# sensor.net
KiCad netlist of a schematic drawn in Altium Designer
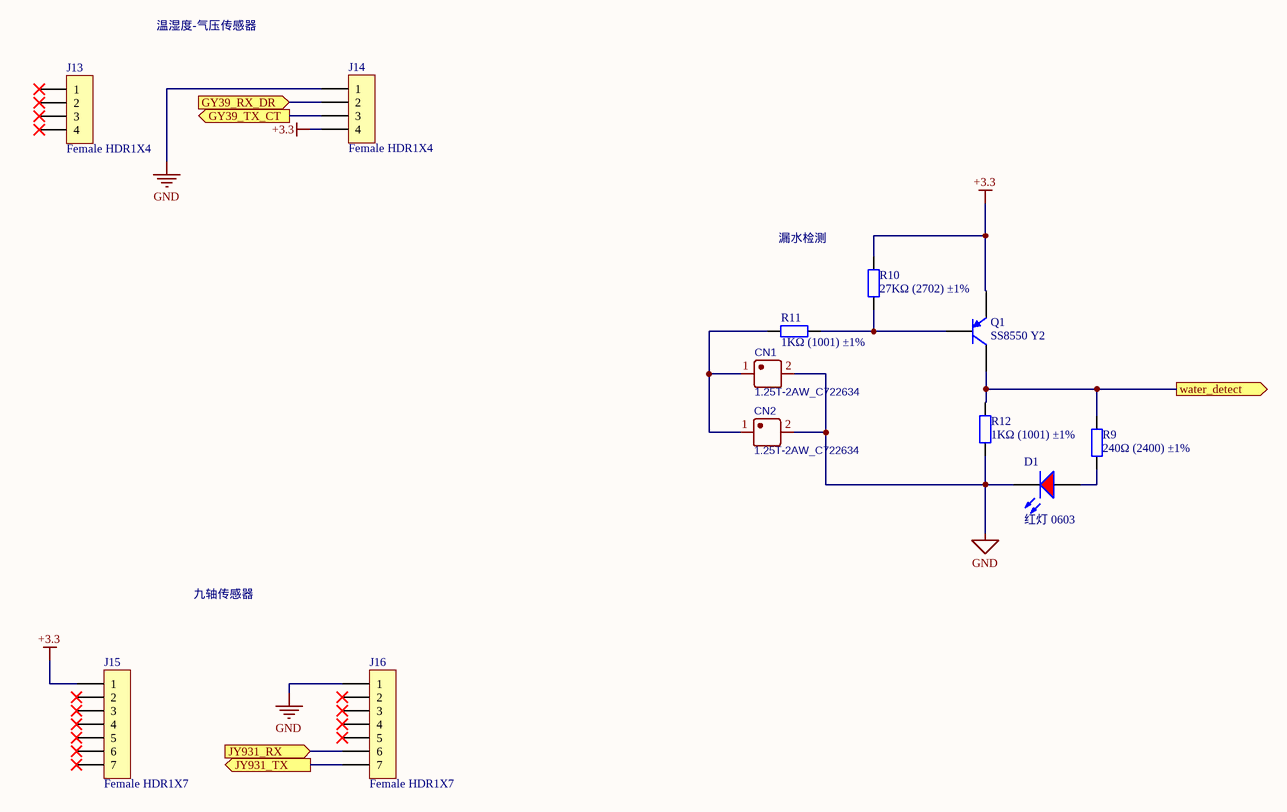
[diagram p0: sensor.SchDoc]

(export (version "E")
  (design (tool "Eeschema 10.0.6"))
  (components
    (comp (ref "CN1")
      (value "1.25T-2AW_C722634")
      (footprint "GH-1.25")
      (fields
        (field (name "BOM_SUPPLIER PART") "C722634")
        (field (name "BOM_MANUFACTURER PART") "1.25T-2AW")
        (field (name "CONTRIBUTOR") "LCSC")
      )
      (libsource (lib "Schlib1") (part "GH 1.25T-2AW_C722634"))
    )
    (comp (ref "CN2")
      (value "1.25T-2AW_C722634")
      (footprint "GH-1.25")
      (fields
        (field (name "BOM_SUPPLIER PART") "C722634")
        (field (name "BOM_MANUFACTURER PART") "1.25T-2AW")
        (field (name "CONTRIBUTOR") "LCSC")
      )
      (libsource (lib "Schlib1") (part "GH 1.25T-2AW_C722634"))
    )
    (comp (ref "D1")
      (value "红灯 0603")
      (footprint "0603_LED_S1")
      (description "发光二极管")
      (libsource (lib "Miscellaneous Devices LC") (part "0603 红灯"))
    )
    (comp (ref "J13")
      (value "Female HDR1X4")
      (footprint "Fe-HDR1X4/2.54-S")
      (libsource (lib "排母") (part "Female HDR1X4"))
    )
    (comp (ref "J14")
      (value "Female HDR1X4")
      (footprint "Fe-HDR1X4/2.54-S")
      (libsource (lib "排母") (part "Female HDR1X4"))
    )
    (comp (ref "J15")
      (value "Female HDR1X7")
      (footprint "Fe-HDR1X7/2.54-S")
      (libsource (lib "排母") (part "Female HDR1X7"))
    )
    (comp (ref "J16")
      (value "Female HDR1X7")
      (footprint "Fe-HDR1X7/2.54-S")
      (libsource (lib "排母") (part "Female HDR1X7"))
    )
    (comp (ref "Q1")
      (value "SS8550 Y2")
      (footprint "SOT-23(SOT-23-3)")
      (description "三极管")
      (libsource (lib "Miscellaneous Devices LC") (part "SOT-23 SS8550 Y2"))
    )
    (comp (ref "R9")
      (value "240Ω (2400) ±1%")
      (footprint "0603_R")
      (description "贴片电阻")
      (libsource (lib "Miscellaneous Devices LC") (part "0603 240Ω (2400) 1%"))
    )
    (comp (ref "R10")
      (value "27KΩ (2702) ±1%")
      (footprint "0603_R")
      (description "贴片电阻")
      (libsource (lib "Miscellaneous Devices LC") (part "0603 27KΩ (2702) 1%"))
    )
    (comp (ref "R11")
      (value "1KΩ (1001) ±1%")
      (footprint "0603_R")
      (description "贴片电阻")
      (libsource (lib "") (part "0603 1KΩ (1001) 1%_1"))
    )
    (comp (ref "R12")
      (value "1KΩ (1001) ±1%")
      (footprint "0603_R")
      (description "贴片电阻")
      (libsource (lib "Miscellaneous Devices LC") (part "0603 1KΩ (1001) 1%"))
    )
  )
  (nets
    (net (code "1") (name "+3.3") (class "Default")
      (node (ref "J14") (pin "4") (pinfunction "4_4") (pintype "passive"))
      (node (ref "J15") (pin "1") (pinfunction "1_1") (pintype "passive"))
      (node (ref "Q1") (pin "2") (pinfunction "E_2") (pintype "passive"))
      (node (ref "R10") (pin "2") (pinfunction "2_2") (pintype "passive"))
    )
    (net (code "2") (name "/GY39_RX_DR") (class "Default")
      (node (ref "J14") (pin "2") (pinfunction "2_2") (pintype "passive"))
    )
    (net (code "3") (name "/GY39_TX_CT") (class "Default")
      (node (ref "J14") (pin "3") (pinfunction "3_3") (pintype "passive"))
    )
    (net (code "4") (name "/JY931_RX") (class "Default")
      (node (ref "J16") (pin "6") (pinfunction "6_6") (pintype "passive"))
    )
    (net (code "5") (name "/JY931_TX") (class "Default")
      (node (ref "J16") (pin "7") (pinfunction "7_7") (pintype "passive"))
    )
    (net (code "6") (name "/water_detect") (class "Default")
      (node (ref "Q1") (pin "3") (pinfunction "C_3") (pintype "passive"))
      (node (ref "R12") (pin "2") (pinfunction "2_2") (pintype "passive"))
      (node (ref "R9") (pin "2") (pinfunction "2_2") (pintype "passive"))
    )
    (net (code "7") (name "GND") (class "Default")
      (node (ref "CN1") (pin "2") (pintype "passive"))
      (node (ref "CN2") (pin "2") (pintype "passive"))
      (node (ref "D1") (pin "K") (pinfunction "K_K") (pintype "passive"))
      (node (ref "J14") (pin "1") (pinfunction "1_1") (pintype "passive"))
      (node (ref "J16") (pin "1") (pinfunction "1_1") (pintype "passive"))
      (node (ref "R12") (pin "1") (pinfunction "1_1") (pintype "passive"))
    )
    (net (code "8") (name "Net-(CN1-Pad1)") (class "Default")
      (node (ref "CN1") (pin "1") (pintype "passive"))
      (node (ref "CN2") (pin "1") (pintype "passive"))
      (node (ref "R11") (pin "1") (pinfunction "1_1") (pintype "passive"))
    )
    (net (code "9") (name "Net-(D1-PadA)") (class "Default")
      (node (ref "D1") (pin "A") (pinfunction "A_A") (pintype "passive"))
      (node (ref "R9") (pin "1") (pinfunction "1_1") (pintype "passive"))
    )
    (net (code "10") (name "Net-(Q1-B)") (class "Default")
      (node (ref "Q1") (pin "1") (pinfunction "B_1") (pintype "passive"))
      (node (ref "R10") (pin "1") (pinfunction "1_1") (pintype "passive"))
      (node (ref "R11") (pin "2") (pinfunction "2_2") (pintype "passive"))
    )
    (net (code "11") (name "unconnected-(J13-Pad1)") (class "Default")
      (node (ref "J13") (pin "1") (pinfunction "1_1") (pintype "passive+no_connect"))
    )
    (net (code "12") (name "unconnected-(J13-Pad2)") (class "Default")
      (node (ref "J13") (pin "2") (pinfunction "2_2") (pintype "passive+no_connect"))
    )
    (net (code "13") (name "unconnected-(J13-Pad3)") (class "Default")
      (node (ref "J13") (pin "3") (pinfunction "3_3") (pintype "passive+no_connect"))
    )
    (net (code "14") (name "unconnected-(J13-Pad4)") (class "Default")
      (node (ref "J13") (pin "4") (pinfunction "4_4") (pintype "passive+no_connect"))
    )
    (net (code "15") (name "unconnected-(J15-Pad2)") (class "Default")
      (node (ref "J15") (pin "2") (pinfunction "2_2") (pintype "passive+no_connect"))
    )
    (net (code "16") (name "unconnected-(J15-Pad3)") (class "Default")
      (node (ref "J15") (pin "3") (pinfunction "3_3") (pintype "passive+no_connect"))
    )
    (net (code "17") (name "unconnected-(J15-Pad4)") (class "Default")
      (node (ref "J15") (pin "4") (pinfunction "4_4") (pintype "passive+no_connect"))
    )
    (net (code "18") (name "unconnected-(J15-Pad5)") (class "Default")
      (node (ref "J15") (pin "5") (pinfunction "5_5") (pintype "passive+no_connect"))
    )
    (net (code "19") (name "unconnected-(J15-Pad6)") (class "Default")
      (node (ref "J15") (pin "6") (pinfunction "6_6") (pintype "passive+no_connect"))
    )
    (net (code "20") (name "unconnected-(J15-Pad7)") (class "Default")
      (node (ref "J15") (pin "7") (pinfunction "7_7") (pintype "passive+no_connect"))
    )
    (net (code "21") (name "unconnected-(J16-Pad2)") (class "Default")
      (node (ref "J16") (pin "2") (pinfunction "2_2") (pintype "passive+no_connect"))
    )
    (net (code "22") (name "unconnected-(J16-Pad3)") (class "Default")
      (node (ref "J16") (pin "3") (pinfunction "3_3") (pintype "passive+no_connect"))
    )
    (net (code "23") (name "unconnected-(J16-Pad4)") (class "Default")
      (node (ref "J16") (pin "4") (pinfunction "4_4") (pintype "passive+no_connect"))
    )
    (net (code "24") (name "unconnected-(J16-Pad5)") (class "Default")
      (node (ref "J16") (pin "5") (pinfunction "5_5") (pintype "passive+no_connect"))
    )
  )
)
